# EVK-IRIS-W1-PIN-HEADERS_SDIO-HEADER.net
KiCad netlist of a schematic drawn in Altium Designer
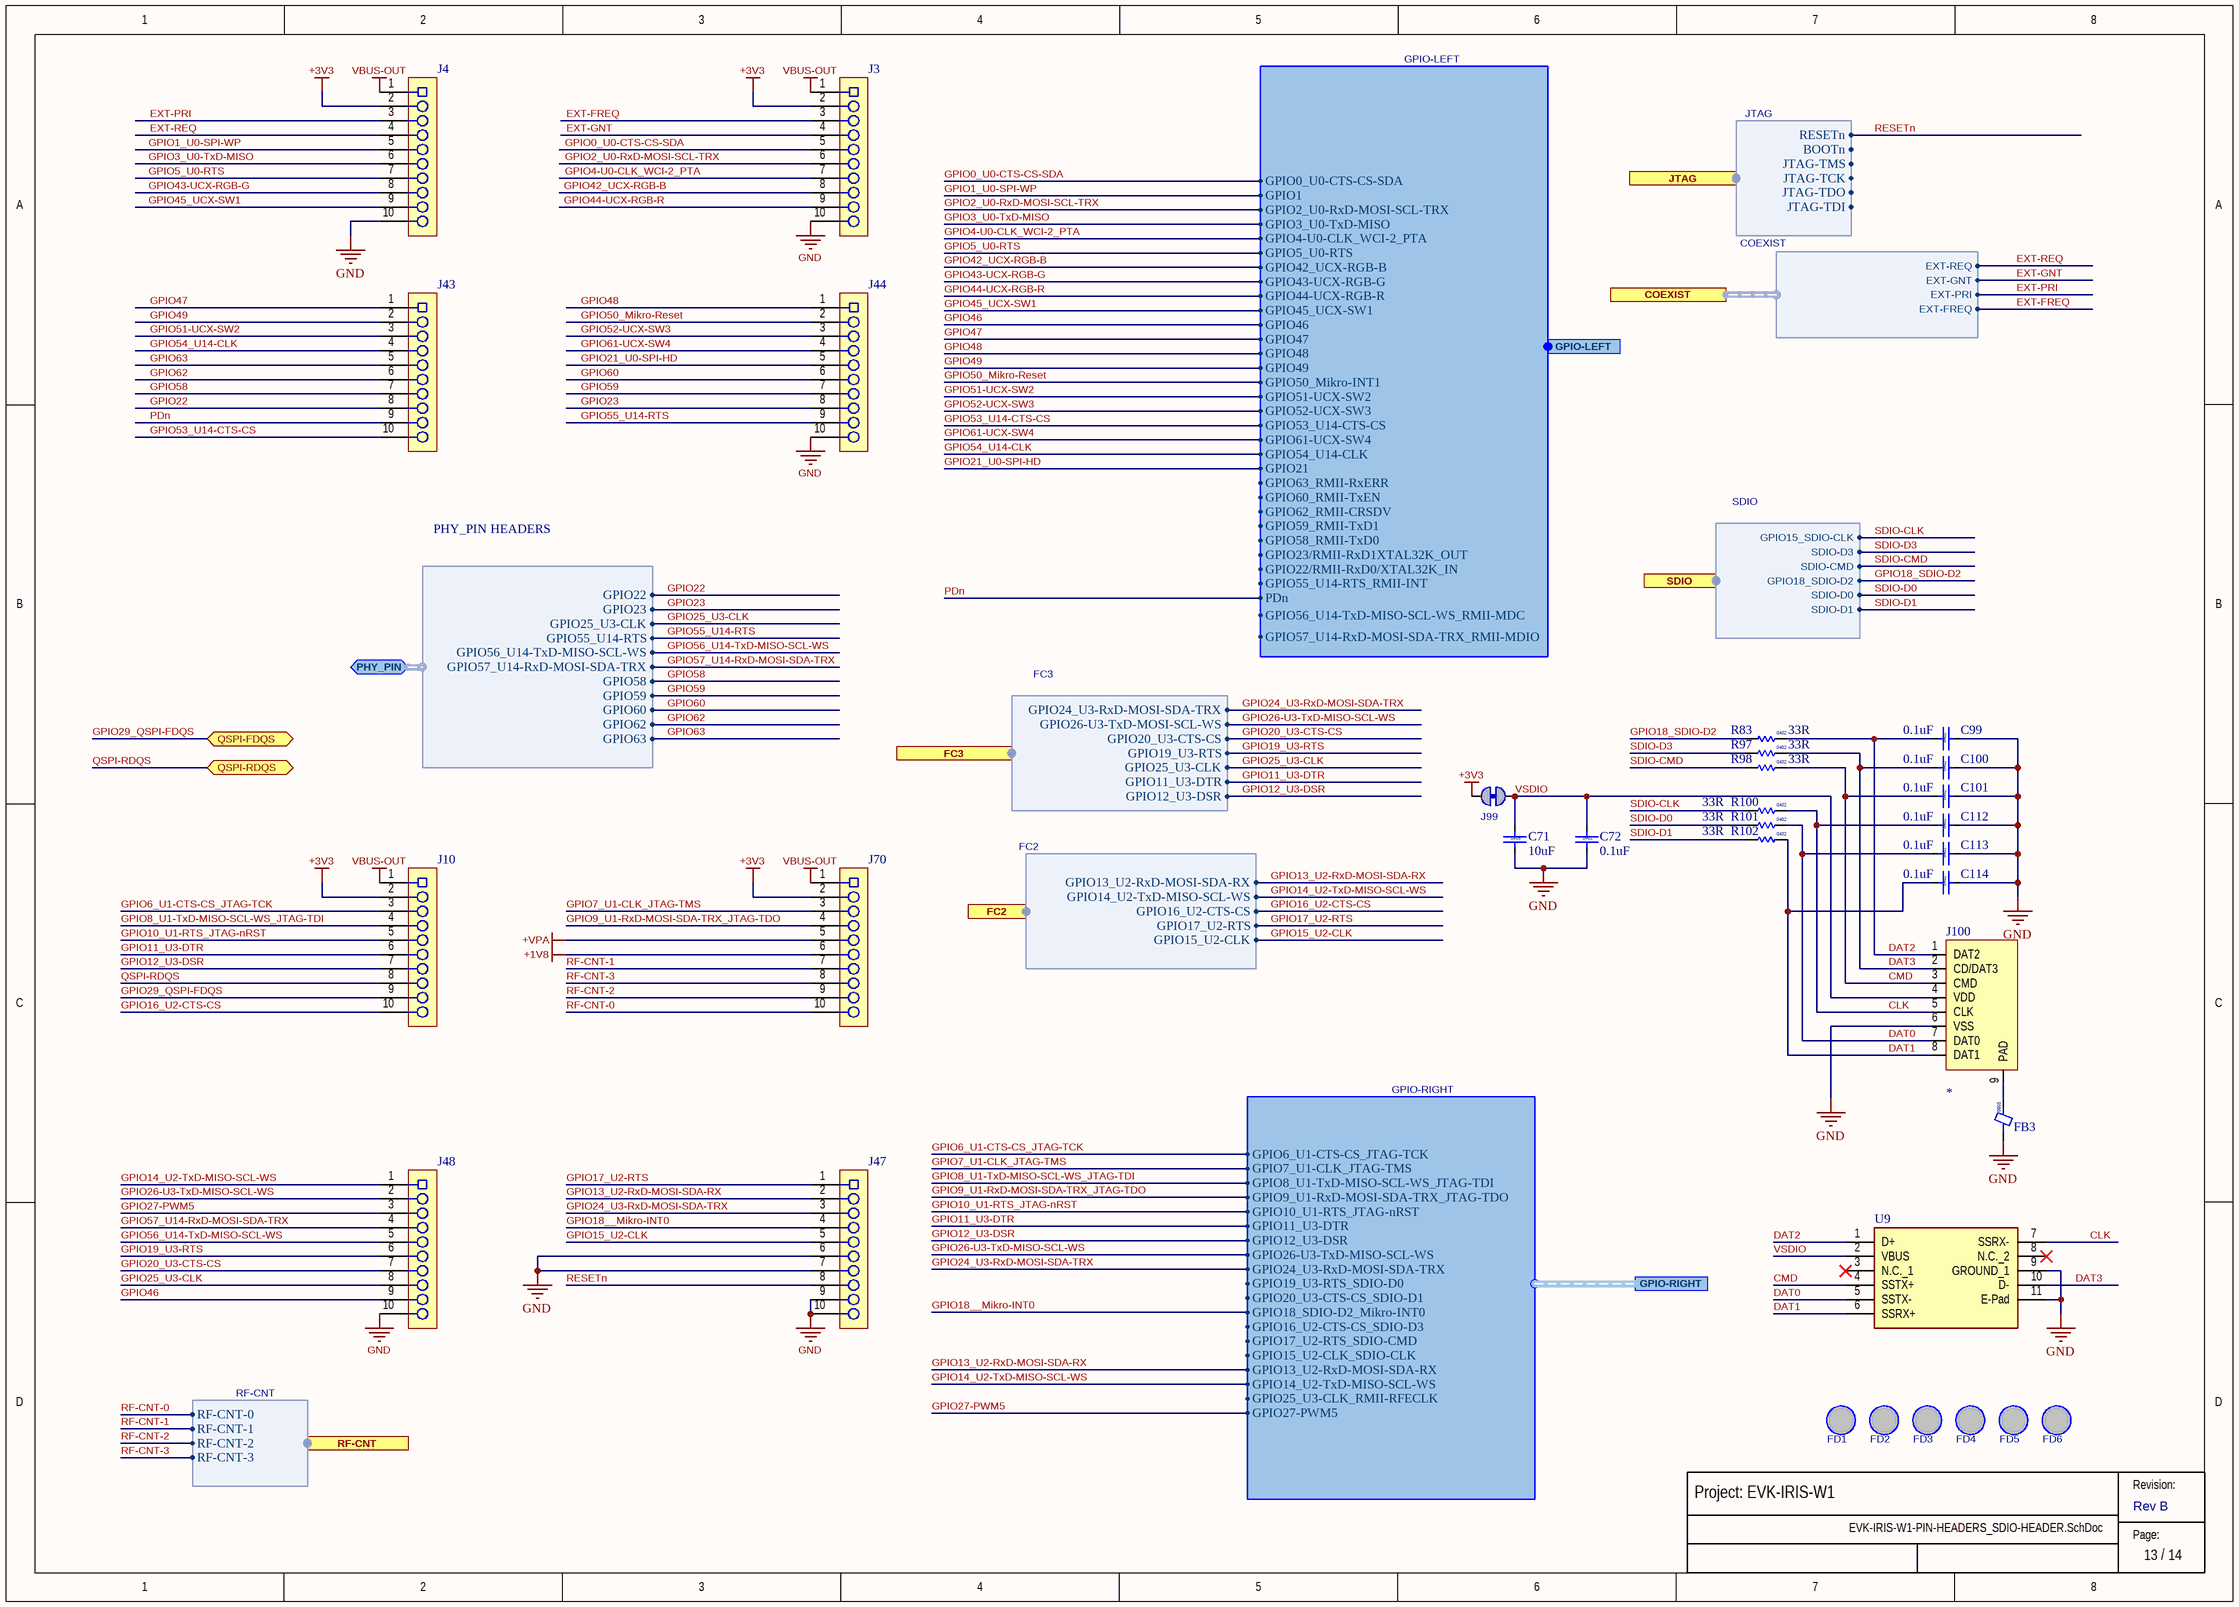
[diagram p0: EVK-IRIS-W1-PIN-HEADERS_SDIO-HEADER.SchDoc]

(export (version "E")
  (design (tool "Eeschema 10.0.6"))
  (components
    (comp (ref "C71")
      (value "10uF")
      (footprint "Cap 0805 HD")
      (description "Capacitor, Ceramic, 10uF 16V 10% X7R, 0805")
      (fields
        (field (name "SIZE") "0805")
        (field (name "PART NUMBER") "120-00133")
        (field (name "TOLERANCE") "+/- 10%")
      )
      (libsource (lib "Arena_Parts_DB_Lib") (part "Cap Chip"))
    )
    (comp (ref "C72")
      (value "0.1uF")
      (footprint "Cap 0402 HD")
      (description "Cap, Ceramic 0.1uF 16V 10% X7R 0402.")
      (fields
        (field (name "SIZE") "0402")
        (field (name "PART NUMBER") "120-00077")
        (field (name "TOLERANCE") "+/- 10%")
      )
      (libsource (lib "Arena_Parts_DB_Lib") (part "Cap Chip"))
    )
    (comp (ref "C99")
      (value "0.1uF")
      (footprint "Cap 0402 HD")
      (description "Cap, Ceramic 0.1uF 16V 10% X7R 0402.")
      (fields
        (field (name "SIZE") "0402")
        (field (name "PART NUMBER") "120-00077")
        (field (name "TOLERANCE") "+/- 10%")
      )
      (libsource (lib "Arena_Parts_DB_Lib") (part "Cap Chip"))
    )
    (comp (ref "C100")
      (value "0.1uF")
      (footprint "Cap 0402 HD")
      (description "Cap, Ceramic 0.1uF 16V 10% X7R 0402.")
      (fields
        (field (name "SIZE") "0402")
        (field (name "PART NUMBER") "120-00077")
        (field (name "TOLERANCE") "+/- 10%")
      )
      (libsource (lib "Arena_Parts_DB_Lib") (part "Cap Chip"))
    )
    (comp (ref "C101")
      (value "0.1uF")
      (footprint "Cap 0402 HD")
      (description "Cap, Ceramic 0.1uF 16V 10% X7R 0402.")
      (fields
        (field (name "SIZE") "0402")
        (field (name "PART NUMBER") "120-00077")
        (field (name "TOLERANCE") "+/- 10%")
      )
      (libsource (lib "Arena_Parts_DB_Lib") (part "Cap Chip"))
    )
    (comp (ref "C112")
      (value "0.1uF")
      (footprint "Cap 0402 HD")
      (description "Cap, Ceramic 0.1uF 16V 10% X7R 0402.")
      (fields
        (field (name "SIZE") "0402")
        (field (name "PART NUMBER") "120-00077")
        (field (name "TOLERANCE") "+/- 10%")
      )
      (libsource (lib "Arena_Parts_DB_Lib") (part "Cap Chip"))
    )
    (comp (ref "C113")
      (value "0.1uF")
      (footprint "Cap 0402 HD")
      (description "Cap, Ceramic 0.1uF 16V 10% X7R 0402.")
      (fields
        (field (name "SIZE") "0402")
        (field (name "PART NUMBER") "120-00077")
        (field (name "TOLERANCE") "+/- 10%")
      )
      (libsource (lib "Arena_Parts_DB_Lib") (part "Cap Chip"))
    )
    (comp (ref "C114")
      (value "0.1uF")
      (footprint "Cap 0402 HD")
      (description "Cap, Ceramic 0.1uF 16V 10% X7R 0402.")
      (fields
        (field (name "SIZE") "0402")
        (field (name "PART NUMBER") "120-00077")
        (field (name "TOLERANCE") "+/- 10%")
      )
      (libsource (lib "Arena_Parts_DB_Lib") (part "Cap Chip"))
    )
    (comp (ref "FB3")
      (value "BLM18EG221SN1")
      (footprint "BLM18EG221SN1")
      (description "Ferrite Bead, 220ohm @ 100MHz, 2A, 0603")
      (fields (field (name "VOLTAGE") "None") (field (name "SIZE") "0603"))
      (libsource (lib "BLM18EG221SN1") (part "BLM18EG221SN1"))
    )
    (comp (ref "FD1")
      (value "Fiducial_1mmDNP")
      (footprint "Fiducial 1mm - Circle")
      (description "1mm Fiducial Target")
      (fields (field (name "PART NUMBER") "Fiducial_1mm") (field (name "ADDED BY") "EMOO"))
      (libsource (lib "PCB_Misc") (part "Fiducial_1mm_Circle"))
    )
    (comp (ref "FD2")
      (value "Fiducial_1mmDNP")
      (footprint "Fiducial 1mm - Circle")
      (description "1mm Fiducial Target")
      (fields (field (name "PART NUMBER") "Fiducial_1mm") (field (name "ADDED BY") "EMOO"))
      (libsource (lib "PCB_Misc") (part "Fiducial_1mm_Circle"))
    )
    (comp (ref "FD3")
      (value "Fiducial_1mmDNP")
      (footprint "Fiducial 1mm - Circle")
      (description "1mm Fiducial Target")
      (fields (field (name "PART NUMBER") "Fiducial_1mm") (field (name "ADDED BY") "EMOO"))
      (libsource (lib "PCB_Misc") (part "Fiducial_1mm_Circle"))
    )
    (comp (ref "FD4")
      (value "Fiducial_1mmDNP")
      (footprint "Fiducial 1mm - Circle")
      (description "1mm Fiducial Target")
      (fields (field (name "PART NUMBER") "Fiducial_1mm") (field (name "ADDED BY") "EMOO"))
      (libsource (lib "PCB_Misc") (part "Fiducial_1mm_Circle"))
    )
    (comp (ref "FD5")
      (value "Fiducial_1mmDNP")
      (footprint "Fiducial 1mm - Circle")
      (description "1mm Fiducial Target")
      (fields (field (name "PART NUMBER") "Fiducial_1mm") (field (name "ADDED BY") "EMOO"))
      (libsource (lib "PCB_Misc") (part "Fiducial_1mm_Circle"))
    )
    (comp (ref "FD6")
      (value "Fiducial_1mmDNP")
      (footprint "Fiducial 1mm - Circle")
      (description "1mm Fiducial Target")
      (fields (field (name "PART NUMBER") "Fiducial_1mm") (field (name "ADDED BY") "EMOO"))
      (libsource (lib "PCB_Misc") (part "Fiducial_1mm_Circle"))
    )
    (comp (ref "J3")
      (value "130-00046")
      (footprint "HDR-0.1P-10PIN-10x1-TH")
      (description "Header, 0.100\" Pitch, 10Pin, 10x1, Through Hole")
      (fields (field (name "VOLTAGE") "None"))
      (libsource (lib "Arena_Parts_DB_Lib") (part "CON-10Pin_1Row"))
    )
    (comp (ref "J4")
      (value "130-00046")
      (footprint "HDR-0.1P-10PIN-10x1-TH")
      (description "Header, 0.100\" Pitch, 10Pin, 10x1, Through Hole")
      (fields (field (name "VOLTAGE") "None"))
      (libsource (lib "Arena_Parts_DB_Lib") (part "CON-10Pin_1Row"))
    )
    (comp (ref "J10")
      (value "130-00046")
      (footprint "HDR-0.1P-10PIN-10x1-TH")
      (description "Header, 0.100\" Pitch, 10Pin, 10x1, Through Hole")
      (fields (field (name "VOLTAGE") "None"))
      (libsource (lib "Arena_Parts_DB_Lib") (part "CON-10Pin_1Row"))
    )
    (comp (ref "J43")
      (value "130-00046")
      (footprint "HDR-0.1P-10PIN-10x1-TH")
      (description "Header, 0.100\" Pitch, 10Pin, 10x1, Through Hole")
      (fields (field (name "VOLTAGE") "None"))
      (libsource (lib "Arena_Parts_DB_Lib") (part "CON-10Pin_1Row"))
    )
    (comp (ref "J44")
      (value "130-00046")
      (footprint "HDR-0.1P-10PIN-10x1-TH")
      (description "Header, 0.100\" Pitch, 10Pin, 10x1, Through Hole")
      (fields (field (name "VOLTAGE") "None"))
      (libsource (lib "Arena_Parts_DB_Lib") (part "CON-10Pin_1Row"))
    )
    (comp (ref "J47")
      (value "130-00046")
      (footprint "HDR-0.1P-10PIN-10x1-TH")
      (description "Header, 0.100\" Pitch, 10Pin, 10x1, Through Hole")
      (fields (field (name "VOLTAGE") "None"))
      (libsource (lib "Arena_Parts_DB_Lib") (part "CON-10Pin_1Row"))
    )
    (comp (ref "J48")
      (value "130-00046")
      (footprint "HDR-0.1P-10PIN-10x1-TH")
      (description "Header, 0.100\" Pitch, 10Pin, 10x1, Through Hole")
      (fields (field (name "VOLTAGE") "None"))
      (libsource (lib "Arena_Parts_DB_Lib") (part "CON-10Pin_1Row"))
    )
    (comp (ref "J70")
      (value "130-00046")
      (footprint "HDR-0.1P-10PIN-10x1-TH")
      (description "Header, 0.100\" Pitch, 10Pin, 10x1, Through Hole")
      (fields (field (name "VOLTAGE") "None"))
      (libsource (lib "Arena_Parts_DB_Lib") (part "CON-10Pin_1Row"))
    )
    (comp (ref "J99")
      (value "Solderbridge-ShortDNP")
      (footprint "Solderbridge-Short")
      (description "Solderbridge-Short")
      (fields (field (name "ADDED BY") "Paul B"))
      (libsource (lib "PCB_Misc") (part "Solderbridge-Short"))
    )
    (comp (ref "J100")
      (value "130-00062")
      (footprint "Micro_SD_SKT_SMT_RA")
      (description "Micro SD Card Socket, Right Angle, with 4 Ground Pads, SMT")
      (fields (field (name "MANUFACTURER P/N") "*") (field (name "VOLTAGE") "None"))
      (libsource (lib "Arena_Parts_DB_Lib") (part "SD_Card_SKT"))
    )
    (comp (ref "R83")
      (value "33R")
      (footprint "RES 0402 HD")
      (description "RES THICK FILM CHIP 0402 33R 5% 50V 63mW")
      (fields
        (field (name "SIZE") "0402")
        (field (name "PART NUMBER") "UBXH18-0008013")
        (field (name "TOLERANCE") "5%")
        (field (name "EDITOR") "matej.budin")
        (field (name "RELEASED BY") "erian.bezhani")
      )
      (libsource (lib "UBX_Parts_DB_Lib") (part "Res sm"))
    )
    (comp (ref "R97")
      (value "33R")
      (footprint "RES 0402 HD")
      (description "RES THICK FILM CHIP 0402 33R 5% 50V 63mW")
      (fields
        (field (name "SIZE") "0402")
        (field (name "PART NUMBER") "UBXH18-0008013")
        (field (name "TOLERANCE") "5%")
        (field (name "EDITOR") "matej.budin")
        (field (name "RELEASED BY") "erian.bezhani")
      )
      (libsource (lib "UBX_Parts_DB_Lib") (part "Res sm"))
    )
    (comp (ref "R98")
      (value "33R")
      (footprint "RES 0402 HD")
      (description "RES THICK FILM CHIP 0402 33R 5% 50V 63mW")
      (fields
        (field (name "SIZE") "0402")
        (field (name "PART NUMBER") "UBXH18-0008013")
        (field (name "TOLERANCE") "5%")
        (field (name "EDITOR") "matej.budin")
        (field (name "RELEASED BY") "erian.bezhani")
      )
      (libsource (lib "UBX_Parts_DB_Lib") (part "Res sm"))
    )
    (comp (ref "R100")
      (value "33R")
      (footprint "RES 0402 HD")
      (description "RES THICK FILM CHIP 0402 33R 5% 50V 63mW")
      (fields
        (field (name "SIZE") "0402")
        (field (name "PART NUMBER") "UBXH18-0008013")
        (field (name "TOLERANCE") "5%")
        (field (name "EDITOR") "matej.budin")
        (field (name "RELEASED BY") "erian.bezhani")
      )
      (libsource (lib "UBX_Parts_DB_Lib") (part "Res sm"))
    )
    (comp (ref "R101")
      (value "33R")
      (footprint "RES 0402 HD")
      (description "RES THICK FILM CHIP 0402 33R 5% 50V 63mW")
      (fields
        (field (name "SIZE") "0402")
        (field (name "PART NUMBER") "UBXH18-0008013")
        (field (name "TOLERANCE") "5%")
        (field (name "EDITOR") "matej.budin")
        (field (name "RELEASED BY") "erian.bezhani")
      )
      (libsource (lib "UBX_Parts_DB_Lib") (part "Res sm"))
    )
    (comp (ref "R102")
      (value "33R")
      (footprint "RES 0402 HD")
      (description "RES THICK FILM CHIP 0402 33R 5% 50V 63mW")
      (fields
        (field (name "SIZE") "0402")
        (field (name "PART NUMBER") "UBXH18-0008013")
        (field (name "TOLERANCE") "5%")
        (field (name "EDITOR") "matej.budin")
        (field (name "RELEASED BY") "erian.bezhani")
      )
      (libsource (lib "UBX_Parts_DB_Lib") (part "Res sm"))
    )
    (comp (ref "U9")
      (value "~")
      (footprint "DFN10")
      (description "4.5V, 7.2V Clamp 4A (8/20µs) Ipp Tvs Diode Surface Mount 10-DFN (4.1x2)")
      (libsource (lib "CDDFN10-0516P") (part "CDDFN10-0516P"))
    )
  )
  (nets
    (net (code "11") (name "+1V8") (class "Default") (node (ref "J70") (pin "6") (pintype "passive")))
    (net (code "12") (name "+3V3") (class "Default")
      (node (ref "J10") (pin "2") (pintype "passive"))
      (node (ref "J3") (pin "2") (pintype "passive"))
      (node (ref "J4") (pin "2") (pintype "passive"))
      (node (ref "J70") (pin "2") (pintype "passive"))
      (node (ref "J99") (pin "1") (pinfunction "1_1") (pintype "passive"))
    )
    (net (code "13") (name "+VPA") (class "Default") (node (ref "J70") (pin "5") (pintype "passive")))
    (net (code "14") (name "/CLK") (class "Default")
      (node (ref "C112") (pin "1") (pinfunction "1_1") (pintype "passive"))
      (node (ref "J100") (pin "5") (pinfunction "CLK_5") (pintype "passive"))
      (node (ref "R100") (pin "2") (pinfunction "2_2") (pintype "passive"))
      (node (ref "U9") (pin "7") (pinfunction "SSRX-_7") (pintype "passive"))
    )
    (net (code "15") (name "/CMD") (class "Default")
      (node (ref "C101") (pin "1") (pinfunction "1_1") (pintype "passive"))
      (node (ref "J100") (pin "3") (pinfunction "CMD_3") (pintype "passive"))
      (node (ref "R98") (pin "2") (pinfunction "2_2") (pintype "passive"))
      (node (ref "U9") (pin "4") (pinfunction "SSTX+_4") (pintype "passive"))
    )
    (net (code "16") (name "/DAT0") (class "Default")
      (node (ref "C113") (pin "1") (pinfunction "1_1") (pintype "passive"))
      (node (ref "J100") (pin "7") (pinfunction "DAT0_7") (pintype "passive"))
      (node (ref "R101") (pin "2") (pinfunction "2_2") (pintype "passive"))
      (node (ref "U9") (pin "5") (pinfunction "SSTX-_5") (pintype "passive"))
    )
    (net (code "17") (name "/DAT1") (class "Default")
      (node (ref "C114") (pin "1") (pinfunction "1_1") (pintype "passive"))
      (node (ref "J100") (pin "8") (pinfunction "DAT1_8") (pintype "passive"))
      (node (ref "R102") (pin "2") (pinfunction "2_2") (pintype "passive"))
      (node (ref "U9") (pin "6") (pinfunction "SSRX+_6") (pintype "passive"))
    )
    (net (code "18") (name "/DAT2") (class "Default")
      (node (ref "C99") (pin "1") (pinfunction "1_1") (pintype "passive"))
      (node (ref "J100") (pin "1") (pinfunction "DAT2_1") (pintype "passive"))
      (node (ref "R83") (pin "2") (pinfunction "2_2") (pintype "passive"))
      (node (ref "U9") (pin "1") (pinfunction "D+_1") (pintype "passive"))
    )
    (net (code "19") (name "/DAT3") (class "Default")
      (node (ref "C100") (pin "1") (pinfunction "1_1") (pintype "passive"))
      (node (ref "J100") (pin "2") (pinfunction "CD/DAT3_2") (pintype "passive"))
      (node (ref "R97") (pin "2") (pinfunction "2_2") (pintype "passive"))
      (node (ref "U9") (pin "10") (pinfunction "D-_10") (pintype "passive"))
    )
    (net (code "20") (name "/EXT-FREQ") (class "Default") (node (ref "J3") (pin "3") (pintype "passive")))
    (net (code "21") (name "/EXT-GNT") (class "Default") (node (ref "J3") (pin "4") (pintype "passive")))
    (net (code "22") (name "/EXT-PRI") (class "Default") (node (ref "J4") (pin "3") (pintype "passive")))
    (net (code "23") (name "/EXT-REQ") (class "Default") (node (ref "J4") (pin "4") (pintype "passive")))
    (net (code "24") (name "/GPIO0_U0-CTS-CS-SDA") (class "Default")
      (node (ref "J3") (pin "5") (pintype "passive"))
    )
    (net (code "25") (name "/GPIO1_U0-SPI-WP") (class "Default")
      (node (ref "J4") (pin "5") (pintype "passive"))
    )
    (net (code "26") (name "/GPIO2_U0-RxD-MOSI-SCL-TRX") (class "Default")
      (node (ref "J3") (pin "6") (pintype "passive"))
    )
    (net (code "27") (name "/GPIO3_U0-TxD-MISO") (class "Default")
      (node (ref "J4") (pin "6") (pintype "passive"))
    )
    (net (code "28") (name "/GPIO4-U0-CLK_WCI-2_PTA") (class "Default")
      (node (ref "J3") (pin "7") (pintype "passive"))
    )
    (net (code "29") (name "/GPIO5_U0-RTS") (class "Default") (node (ref "J4") (pin "7") (pintype "passive")))
    (net (code "30") (name "/GPIO6_U1-CTS-CS_JTAG-TCK") (class "Default")
      (node (ref "J10") (pin "3") (pintype "passive"))
    )
    (net (code "31") (name "/GPIO7_U1-CLK_JTAG-TMS") (class "Default")
      (node (ref "J70") (pin "3") (pintype "passive"))
    )
    (net (code "32") (name "/GPIO8_U1-TxD-MISO-SCL-WS_JTAG-TDI") (class "Default")
      (node (ref "J10") (pin "4") (pintype "passive"))
    )
    (net (code "33") (name "/GPIO9_U1-RxD-MOSI-SDA-TRX_JTAG-TDO") (class "Default")
      (node (ref "J70") (pin "4") (pintype "passive"))
    )
    (net (code "34") (name "/GPIO10_U1-RTS_JTAG-nRST") (class "Default")
      (node (ref "J10") (pin "5") (pintype "passive"))
    )
    (net (code "35") (name "/GPIO11_U3-DTR") (class "Default")
      (node (ref "J10") (pin "6") (pintype "passive"))
    )
    (net (code "36") (name "/GPIO12_U3-DSR") (class "Default")
      (node (ref "J10") (pin "7") (pintype "passive"))
    )
    (net (code "37") (name "/GPIO13_U2-RxD-MOSI-SDA-RX") (class "Default")
      (node (ref "J47") (pin "2") (pintype "passive"))
    )
    (net (code "38") (name "/GPIO14_U2-TxD-MISO-SCL-WS") (class "Default")
      (node (ref "J48") (pin "1") (pintype "passive"))
    )
    (net (code "39") (name "/GPIO15_U2-CLK") (class "Default")
      (node (ref "J47") (pin "5") (pintype "passive"))
    )
    (net (code "40") (name "/GPIO16_U2-CTS-CS") (class "Default")
      (node (ref "J10") (pin "10") (pintype "passive"))
    )
    (net (code "41") (name "/GPIO17_U2-RTS") (class "Default")
      (node (ref "J47") (pin "1") (pintype "passive"))
    )
    (net (code "42") (name "/GPIO18_SDIO-D2") (class "Default")
      (node (ref "R83") (pin "1") (pinfunction "1_1") (pintype "passive"))
    )
    (net (code "43") (name "/GPIO18__Mikro-INT0") (class "Default")
      (node (ref "J47") (pin "4") (pintype "passive"))
    )
    (net (code "44") (name "/GPIO19_U3-RTS") (class "Default")
      (node (ref "J48") (pin "6") (pintype "passive"))
    )
    (net (code "45") (name "/GPIO20_U3-CTS-CS") (class "Default")
      (node (ref "J48") (pin "7") (pintype "passive"))
    )
    (net (code "46") (name "/GPIO21_U0-SPI-HD") (class "Default")
      (node (ref "J44") (pin "5") (pintype "passive"))
    )
    (net (code "47") (name "/GPIO22") (class "Default") (node (ref "J43") (pin "8") (pintype "passive")))
    (net (code "48") (name "/GPIO23") (class "Default") (node (ref "J44") (pin "8") (pintype "passive")))
    (net (code "49") (name "/GPIO24_U3-RxD-MOSI-SDA-TRX") (class "Default")
      (node (ref "J47") (pin "3") (pintype "passive"))
    )
    (net (code "50") (name "/GPIO25_U3-CLK") (class "Default")
      (node (ref "J48") (pin "8") (pintype "passive"))
    )
    (net (code "51") (name "/GPIO26-U3-TxD-MISO-SCL-WS") (class "Default")
      (node (ref "J48") (pin "2") (pintype "passive"))
    )
    (net (code "52") (name "/GPIO27-PWM5") (class "Default") (node (ref "J48") (pin "3") (pintype "passive")))
    (net (code "53") (name "/GPIO29_QSPI-FDQS") (class "Default")
      (node (ref "J10") (pin "9") (pintype "passive"))
    )
    (net (code "54") (name "/GPIO42_UCX-RGB-B") (class "Default")
      (node (ref "J3") (pin "8") (pintype "passive"))
    )
    (net (code "55") (name "/GPIO43-UCX-RGB-G") (class "Default")
      (node (ref "J4") (pin "8") (pintype "passive"))
    )
    (net (code "56") (name "/GPIO44-UCX-RGB-R") (class "Default")
      (node (ref "J3") (pin "9") (pintype "passive"))
    )
    (net (code "57") (name "/GPIO45_UCX-SW1") (class "Default")
      (node (ref "J4") (pin "9") (pintype "passive"))
    )
    (net (code "58") (name "/GPIO46") (class "Default") (node (ref "J48") (pin "9") (pintype "passive")))
    (net (code "59") (name "/GPIO47") (class "Default") (node (ref "J43") (pin "1") (pintype "passive")))
    (net (code "60") (name "/GPIO48") (class "Default") (node (ref "J44") (pin "1") (pintype "passive")))
    (net (code "61") (name "/GPIO49") (class "Default") (node (ref "J43") (pin "2") (pintype "passive")))
    (net (code "62") (name "/GPIO50_Mikro-Reset") (class "Default")
      (node (ref "J44") (pin "2") (pintype "passive"))
    )
    (net (code "63") (name "/GPIO51-UCX-SW2") (class "Default")
      (node (ref "J43") (pin "3") (pintype "passive"))
    )
    (net (code "64") (name "/GPIO52-UCX-SW3") (class "Default")
      (node (ref "J44") (pin "3") (pintype "passive"))
    )
    (net (code "65") (name "/GPIO53_U14-CTS-CS") (class "Default")
      (node (ref "J43") (pin "10") (pintype "passive"))
    )
    (net (code "66") (name "/GPIO54_U14-CLK") (class "Default")
      (node (ref "J43") (pin "4") (pintype "passive"))
    )
    (net (code "67") (name "/GPIO55_U14-RTS") (class "Default")
      (node (ref "J44") (pin "9") (pintype "passive"))
    )
    (net (code "68") (name "/GPIO56_U14-TxD-MISO-SCL-WS") (class "Default")
      (node (ref "J48") (pin "5") (pintype "passive"))
    )
    (net (code "69") (name "/GPIO57_U14-RxD-MOSI-SDA-TRX") (class "Default")
      (node (ref "J48") (pin "4") (pintype "passive"))
    )
    (net (code "70") (name "/GPIO58") (class "Default") (node (ref "J43") (pin "7") (pintype "passive")))
    (net (code "71") (name "/GPIO59") (class "Default") (node (ref "J44") (pin "7") (pintype "passive")))
    (net (code "72") (name "/GPIO60") (class "Default") (node (ref "J44") (pin "6") (pintype "passive")))
    (net (code "73") (name "/GPIO61-UCX-SW4") (class "Default")
      (node (ref "J44") (pin "4") (pintype "passive"))
    )
    (net (code "74") (name "/GPIO62") (class "Default") (node (ref "J43") (pin "6") (pintype "passive")))
    (net (code "75") (name "/GPIO63") (class "Default") (node (ref "J43") (pin "5") (pintype "passive")))
    (net (code "76") (name "/PDn") (class "Default") (node (ref "J43") (pin "9") (pintype "passive")))
    (net (code "77") (name "/QSPI-RDQS") (class "Default") (node (ref "J10") (pin "8") (pintype "passive")))
    (net (code "78") (name "/RESETn") (class "Default") (node (ref "J47") (pin "8") (pintype "passive")))
    (net (code "79") (name "/RF-CNT-0") (class "Default") (node (ref "J70") (pin "10") (pintype "passive")))
    (net (code "80") (name "/RF-CNT-1") (class "Default") (node (ref "J70") (pin "7") (pintype "passive")))
    (net (code "81") (name "/RF-CNT-2") (class "Default") (node (ref "J70") (pin "9") (pintype "passive")))
    (net (code "82") (name "/RF-CNT-3") (class "Default") (node (ref "J70") (pin "8") (pintype "passive")))
    (net (code "83") (name "/SDIO-CLK") (class "Default")
      (node (ref "R100") (pin "1") (pinfunction "1_1") (pintype "passive"))
    )
    (net (code "84") (name "/SDIO-CMD") (class "Default")
      (node (ref "R98") (pin "1") (pinfunction "1_1") (pintype "passive"))
    )
    (net (code "85") (name "/SDIO-D0") (class "Default")
      (node (ref "R101") (pin "1") (pinfunction "1_1") (pintype "passive"))
    )
    (net (code "86") (name "/SDIO-D1") (class "Default")
      (node (ref "R102") (pin "1") (pinfunction "1_1") (pintype "passive"))
    )
    (net (code "87") (name "/SDIO-D3") (class "Default")
      (node (ref "R97") (pin "1") (pinfunction "1_1") (pintype "passive"))
    )
    (net (code "88") (name "/VSDIO") (class "Default")
      (node (ref "C71") (pin "1") (pinfunction "1_1") (pintype "passive"))
      (node (ref "C72") (pin "1") (pinfunction "1_1") (pintype "passive"))
      (node (ref "J100") (pin "4") (pinfunction "VDD_4") (pintype "power_in"))
      (node (ref "J99") (pin "2") (pinfunction "2_2") (pintype "passive"))
      (node (ref "U9") (pin "2") (pinfunction "VBUS_2") (pintype "passive"))
    )
    (net (code "98") (name "GND") (class "Default")
      (node (ref "C100") (pin "2") (pinfunction "2_2") (pintype "passive"))
      (node (ref "C101") (pin "2") (pinfunction "2_2") (pintype "passive"))
      (node (ref "C112") (pin "2") (pinfunction "2_2") (pintype "passive"))
      (node (ref "C113") (pin "2") (pinfunction "2_2") (pintype "passive"))
      (node (ref "C114") (pin "2") (pinfunction "2_2") (pintype "passive"))
      (node (ref "C71") (pin "2") (pinfunction "2_2") (pintype "passive"))
      (node (ref "C72") (pin "2") (pinfunction "2_2") (pintype "passive"))
      (node (ref "C99") (pin "2") (pinfunction "2_2") (pintype "passive"))
      (node (ref "FB3") (pin "1") (pinfunction "1_1") (pintype "passive"))
      (node (ref "J100") (pin "6") (pinfunction "VSS_6") (pintype "power_in"))
      (node (ref "J3") (pin "10") (pintype "passive"))
      (node (ref "J4") (pin "10") (pintype "passive"))
      (node (ref "J44") (pin "10") (pintype "passive"))
      (node (ref "J47") (pin "10") (pintype "passive"))
      (node (ref "J47") (pin "6") (pintype "passive"))
      (node (ref "J47") (pin "7") (pintype "passive"))
      (node (ref "J47") (pin "9") (pintype "passive"))
      (node (ref "J48") (pin "10") (pintype "passive"))
      (node (ref "U9") (pin "11") (pinfunction "E-Pad_11") (pintype "passive"))
      (node (ref "U9") (pin "9") (pinfunction "GROUND_1_9") (pintype "passive"))
    )
    (net (code "99") (name "Net-(J100-PAD)") (class "Default")
      (node (ref "FB3") (pin "2") (pinfunction "2_2") (pintype "passive"))
      (node (ref "J100") (pin "9") (pinfunction "PAD_9") (pintype "power_in"))
    )
    (net (code "100") (name "VBUS-OUT") (class "Default")
      (node (ref "J10") (pin "1") (pintype "passive"))
      (node (ref "J3") (pin "1") (pintype "passive"))
      (node (ref "J4") (pin "1") (pintype "passive"))
      (node (ref "J70") (pin "1") (pintype "passive"))
    )
    (net (code "101") (name "unconnected-(U9-N.C._1-Pad3)") (class "Default")
      (node (ref "U9") (pin "3") (pinfunction "N.C._1_3") (pintype "passive+no_connect"))
    )
    (net (code "102") (name "unconnected-(U9-N.C._2-Pad8)") (class "Default")
      (node (ref "U9") (pin "8") (pinfunction "N.C._2_8") (pintype "passive+no_connect"))
    )
  )
)
